# STM32H730_PINOUT.net
KiCad netlist of a schematic drawn in Altium Designer
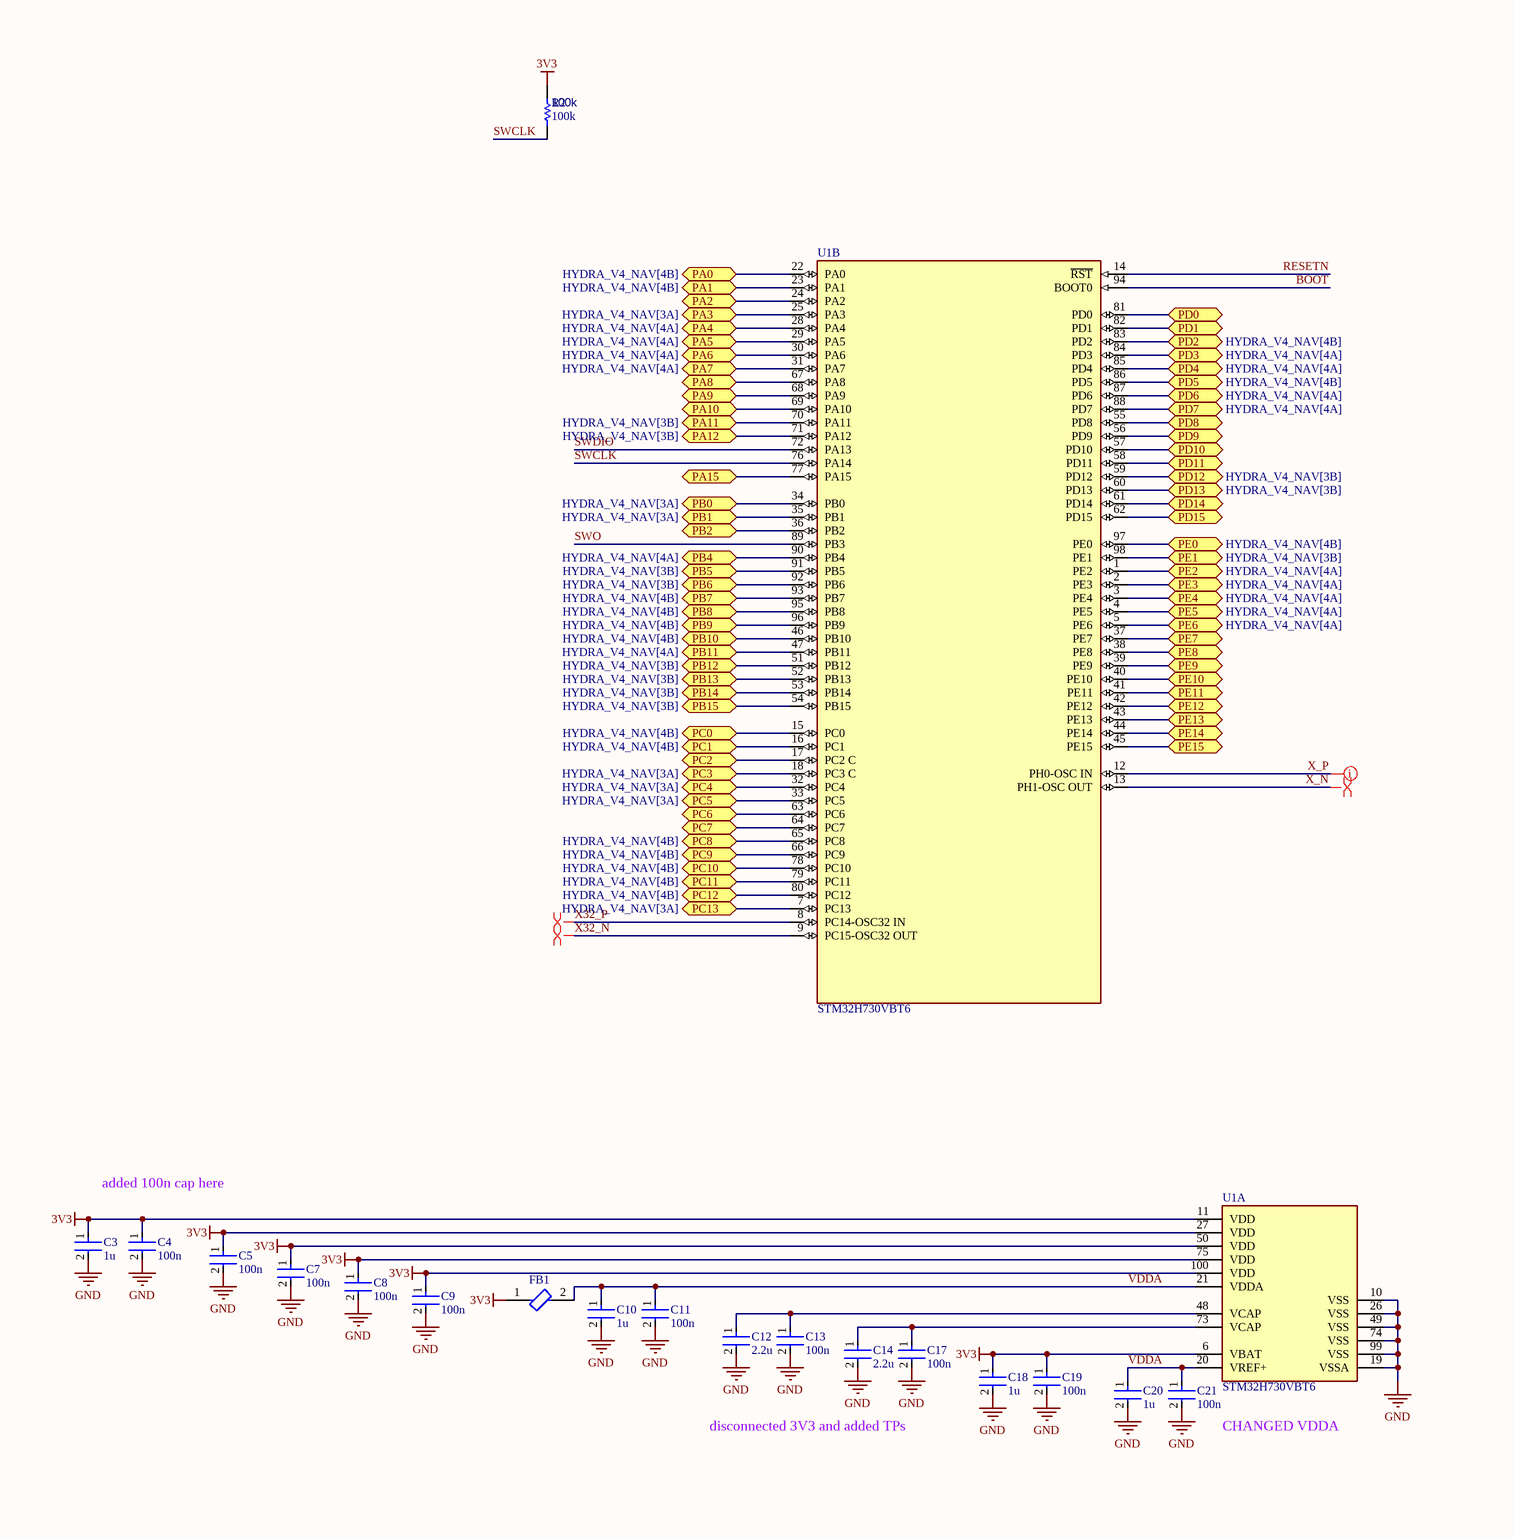
[diagram p0: STM32H730_PINOUT.SchDoc, left]
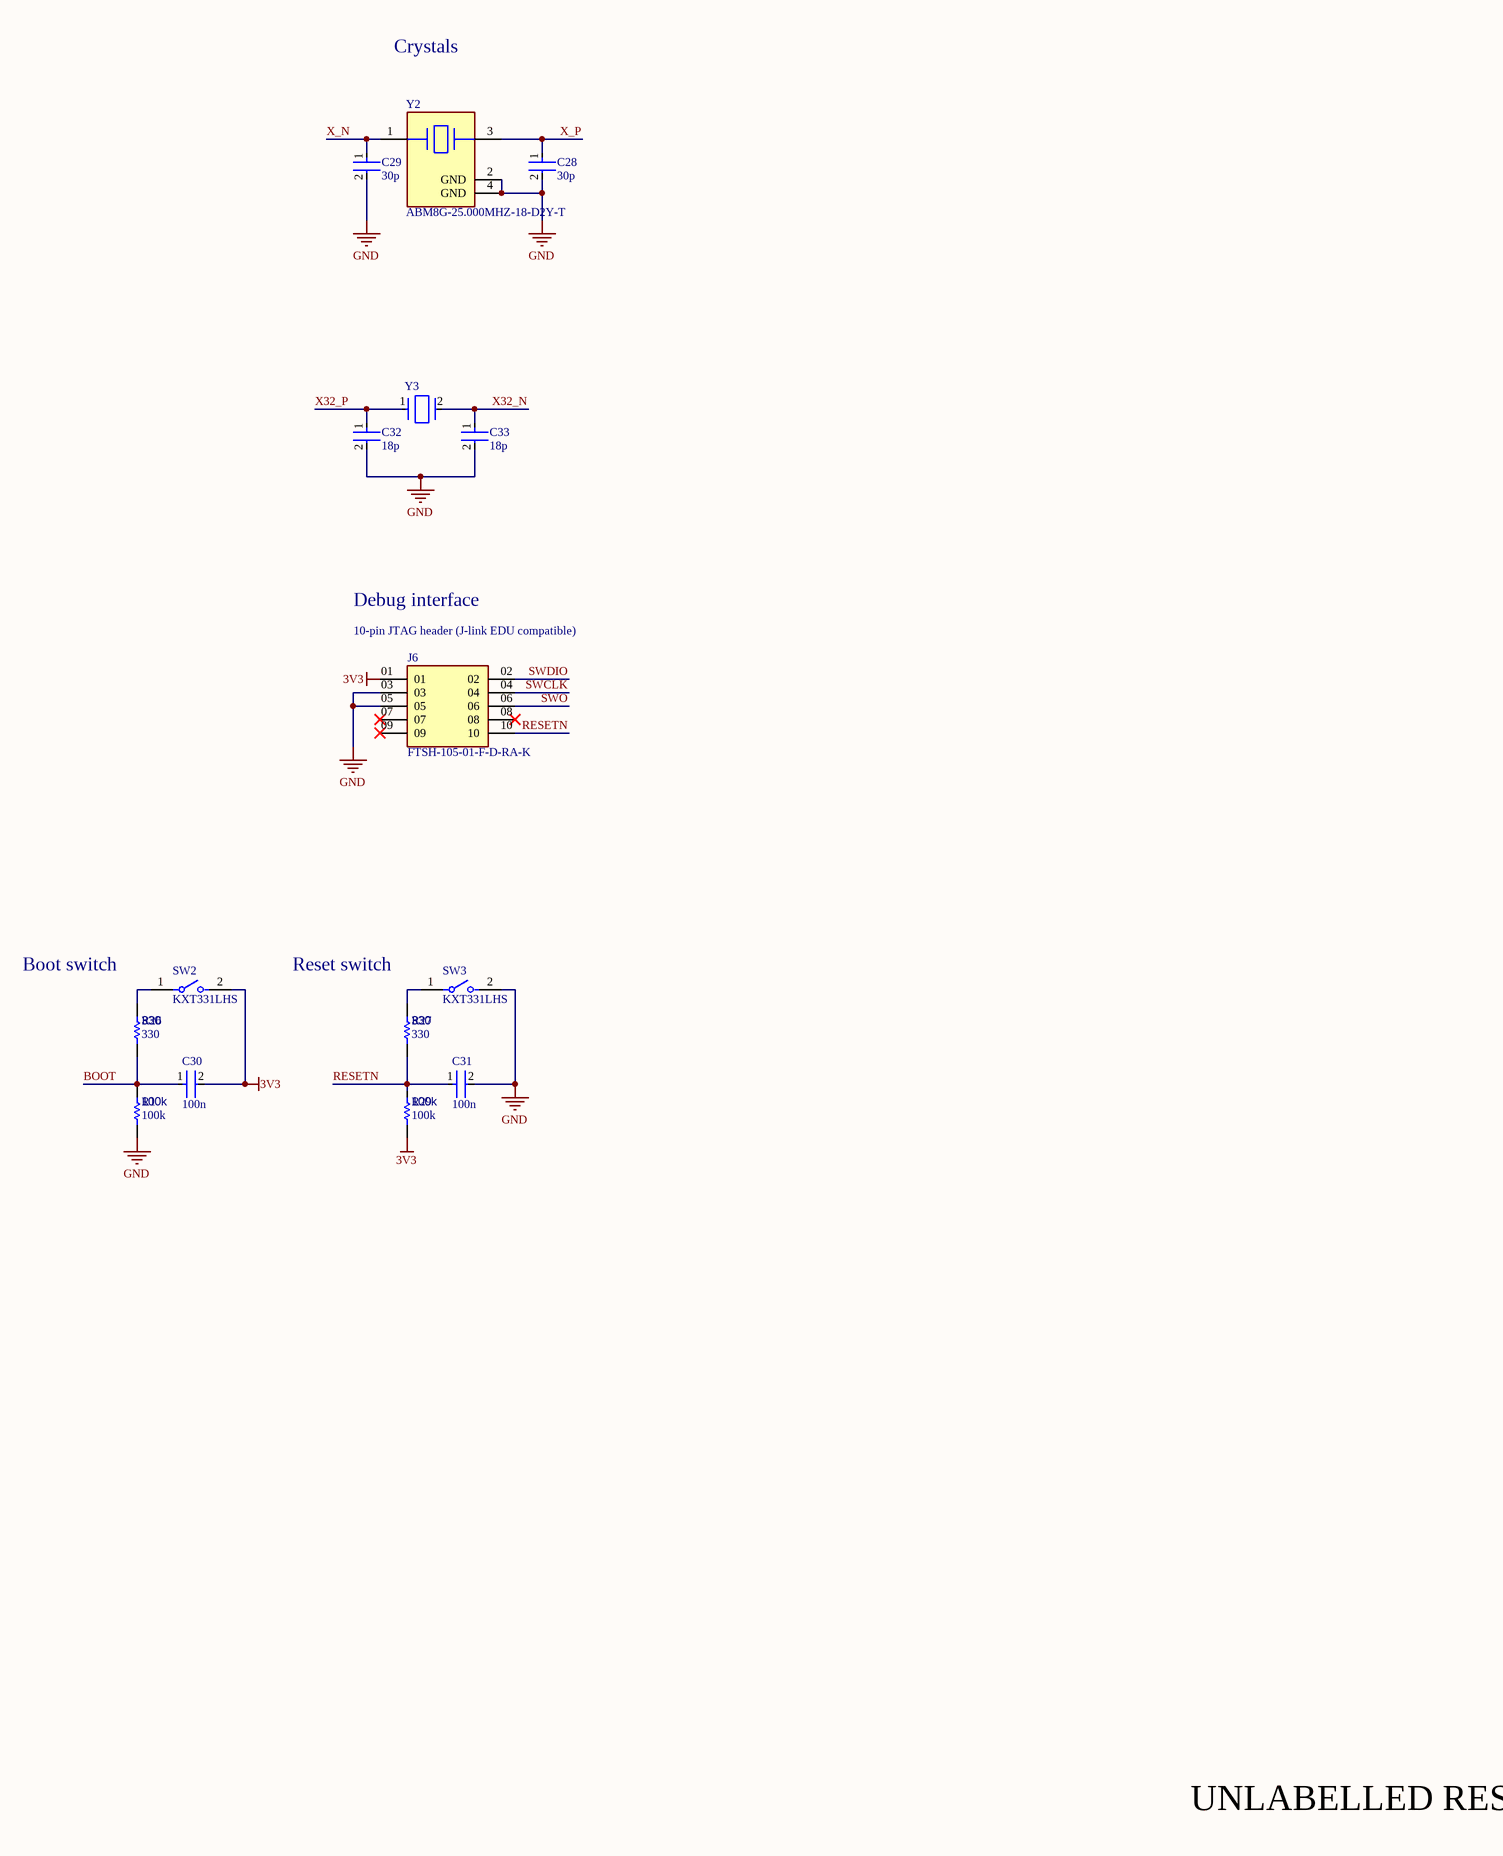
[diagram p1: STM32H730_PINOUT.SchDoc, right]

(export (version "E")
  (design (tool "Eeschema 10.0.6"))
  (components
    (comp (ref "C3")
      (value "1u")
      (footprint "FP-0402-L_1_0_0_05-W_0_5-IPC_A")
      (description "LARGE PADS, 0402 CAP, CHANGE COMMENT TO MATCH REAL P/N")
      (libsource (lib "Space Concordia") (part "b4654b650e69147ec39a6b967a45e02"))
    )
    (comp (ref "C4")
      (value "100n")
      (footprint "FP-0402-L_1_0_0_05-W_0_5-IPC_A")
      (description "LARGE PADS, 0402 CAP, CHANGE COMMENT TO MATCH REAL P/N")
      (libsource (lib "Space Concordia") (part "b4654b650e69147ec39a6b967a45e02"))
    )
    (comp (ref "C5")
      (value "100n")
      (footprint "FP-0402-L_1_0_0_05-W_0_5-IPC_A")
      (description "LARGE PADS, 0402 CAP, CHANGE COMMENT TO MATCH REAL P/N")
      (libsource (lib "Space Concordia") (part "b4654b650e69147ec39a6b967a45e02"))
    )
    (comp (ref "C7")
      (value "100n")
      (footprint "FP-0402-L_1_0_0_05-W_0_5-IPC_A")
      (description "LARGE PADS, 0402 CAP, CHANGE COMMENT TO MATCH REAL P/N")
      (libsource (lib "Space Concordia") (part "b4654b650e69147ec39a6b967a45e02"))
    )
    (comp (ref "C8")
      (value "100n")
      (footprint "FP-0402-L_1_0_0_05-W_0_5-IPC_A")
      (description "LARGE PADS, 0402 CAP, CHANGE COMMENT TO MATCH REAL P/N")
      (libsource (lib "Space Concordia") (part "b4654b650e69147ec39a6b967a45e02"))
    )
    (comp (ref "C9")
      (value "100n")
      (footprint "FP-0402-L_1_0_0_05-W_0_5-IPC_A")
      (description "LARGE PADS, 0402 CAP, CHANGE COMMENT TO MATCH REAL P/N")
      (libsource (lib "Space Concordia") (part "b4654b650e69147ec39a6b967a45e02"))
    )
    (comp (ref "C10")
      (value "1u")
      (footprint "FP-0402-L_1_0_0_05-W_0_5-IPC_A")
      (description "LARGE PADS, 0402 CAP, CHANGE COMMENT TO MATCH REAL P/N")
      (libsource (lib "Space Concordia") (part "b4654b650e69147ec39a6b967a45e02"))
    )
    (comp (ref "C11")
      (value "100n")
      (footprint "FP-0402-L_1_0_0_05-W_0_5-IPC_A")
      (description "LARGE PADS, 0402 CAP, CHANGE COMMENT TO MATCH REAL P/N")
      (libsource (lib "Space Concordia") (part "b4654b650e69147ec39a6b967a45e02"))
    )
    (comp (ref "C12")
      (value "2.2u")
      (footprint "FP-0402-L_1_0_0_05-W_0_5-IPC_A")
      (description "LARGE PADS, 0402 CAP, CHANGE COMMENT TO MATCH REAL P/N")
      (libsource (lib "Space Concordia") (part "b4654b650e69147ec39a6b967a45e02"))
    )
    (comp (ref "C13")
      (value "100n")
      (footprint "FP-0402-L_1_0_0_05-W_0_5-IPC_A")
      (description "LARGE PADS, 0402 CAP, CHANGE COMMENT TO MATCH REAL P/N")
      (libsource (lib "Space Concordia") (part "b4654b650e69147ec39a6b967a45e02"))
    )
    (comp (ref "C14")
      (value "2.2u")
      (footprint "FP-0402-L_1_0_0_05-W_0_5-IPC_A")
      (description "LARGE PADS, 0402 CAP, CHANGE COMMENT TO MATCH REAL P/N")
      (libsource (lib "Space Concordia") (part "b4654b650e69147ec39a6b967a45e02"))
    )
    (comp (ref "C17")
      (value "100n")
      (footprint "FP-0402-L_1_0_0_05-W_0_5-IPC_A")
      (description "LARGE PADS, 0402 CAP, CHANGE COMMENT TO MATCH REAL P/N")
      (libsource (lib "Space Concordia") (part "b4654b650e69147ec39a6b967a45e02"))
    )
    (comp (ref "C18")
      (value "1u")
      (footprint "FP-0402-L_1_0_0_05-W_0_5-IPC_A")
      (description "LARGE PADS, 0402 CAP, CHANGE COMMENT TO MATCH REAL P/N")
      (libsource (lib "Space Concordia") (part "b4654b650e69147ec39a6b967a45e02"))
    )
    (comp (ref "C19")
      (value "100n")
      (footprint "FP-0402-L_1_0_0_05-W_0_5-IPC_A")
      (description "LARGE PADS, 0402 CAP, CHANGE COMMENT TO MATCH REAL P/N")
      (libsource (lib "Space Concordia") (part "b4654b650e69147ec39a6b967a45e02"))
    )
    (comp (ref "C20")
      (value "1u")
      (footprint "FP-0402-L_1_0_0_05-W_0_5-IPC_A")
      (description "LARGE PADS, 0402 CAP, CHANGE COMMENT TO MATCH REAL P/N")
      (libsource (lib "Space Concordia") (part "b4654b650e69147ec39a6b967a45e02"))
    )
    (comp (ref "C21")
      (value "100n")
      (footprint "FP-0402-L_1_0_0_05-W_0_5-IPC_A")
      (description "LARGE PADS, 0402 CAP, CHANGE COMMENT TO MATCH REAL P/N")
      (libsource (lib "Space Concordia") (part "b4654b650e69147ec39a6b967a45e02"))
    )
    (comp (ref "C28")
      (value "30p")
      (footprint "FP-0402-L_1_0_0_05-W_0_5-IPC_A")
      (description "LARGE PADS, 0402 CAP, CHANGE COMMENT TO MATCH REAL P/N")
      (libsource (lib "Space Concordia") (part "b4654b650e69147ec39a6b967a45e02"))
    )
    (comp (ref "C29")
      (value "30p")
      (footprint "FP-0402-L_1_0_0_05-W_0_5-IPC_A")
      (description "LARGE PADS, 0402 CAP, CHANGE COMMENT TO MATCH REAL P/N")
      (libsource (lib "Space Concordia") (part "b4654b650e69147ec39a6b967a45e02"))
    )
    (comp (ref "C30")
      (value "100n")
      (footprint "FP-0402-L_1_0_0_05-W_0_5-IPC_A")
      (description "LARGE PADS, 0402 CAP, CHANGE COMMENT TO MATCH REAL P/N")
      (libsource (lib "Space Concordia") (part "b4654b650e69147ec39a6b967a45e02"))
    )
    (comp (ref "C31")
      (value "100n")
      (footprint "FP-0402-L_1_0_0_05-W_0_5-IPC_A")
      (description "LARGE PADS, 0402 CAP, CHANGE COMMENT TO MATCH REAL P/N")
      (libsource (lib "Space Concordia") (part "b4654b650e69147ec39a6b967a45e02"))
    )
    (comp (ref "C32")
      (value "18p")
      (footprint "FP-0402-L_1_0_0_05-W_0_5-IPC_A")
      (description "LARGE PADS, 0402 CAP, CHANGE COMMENT TO MATCH REAL P/N")
      (libsource (lib "Space Concordia") (part "b4654b650e69147ec39a6b967a45e02"))
    )
    (comp (ref "C33")
      (value "18p")
      (footprint "FP-0402-L_1_0_0_05-W_0_5-IPC_A")
      (description "LARGE PADS, 0402 CAP, CHANGE COMMENT TO MATCH REAL P/N")
      (libsource (lib "Space Concordia") (part "b4654b650e69147ec39a6b967a45e02"))
    )
    (comp (ref "FB1")
      (value "BLM15PX601SN1D")
      (footprint "FP-BLM15-0_05-MFG")
      (description "Chip Ferrite Bead, 0402, 600Ω @ 100MHz, 0.23Ω, 25%, 900mA")
      (fields (field (name "TOLERANCE") "25%"))
      (libsource (lib "Altium Content Vault") (part "5f30dd21d616792df468990f7003faa"))
    )
    (comp (ref "J6")
      (value "FTSH-105-01-F-D-RA-K")
      (footprint "FTSH-105-01-F-D-RA-K-Footprint-1")
      (libsource (lib "Space Concordia") (part "FTSH-105-01-F-D-RA-K-Symbol-1"))
    )
    (comp (ref "R1")
      (value "100k")
      (footprint "R0603B")
      (description "Resistor")
      (fields (field (name "ALTIUM_VALUE") "100k"))
      (libsource (lib "Space Concordia") (part "Resistor"))
    )
    (comp (ref "R2")
      (value "100k")
      (footprint "R0603B")
      (description "Resistor")
      (fields (field (name "ALTIUM_VALUE") "100k"))
      (libsource (lib "Space Concordia") (part "Resistor"))
    )
    (comp (ref "R26")
      (value "330")
      (footprint "R0603B")
      (description "Resistor")
      (fields (field (name "ALTIUM_VALUE") "330"))
      (libsource (lib "Space Concordia") (part "Resistor"))
    )
    (comp (ref "R27")
      (value "330")
      (footprint "R0603B")
      (description "Resistor")
      (fields (field (name "ALTIUM_VALUE") "330"))
      (libsource (lib "Space Concordia") (part "Resistor"))
    )
    (comp (ref "R29")
      (value "100k")
      (footprint "R0603B")
      (description "Resistor")
      (fields (field (name "ALTIUM_VALUE") "100k"))
      (libsource (lib "Space Concordia") (part "Resistor"))
    )
    (comp (ref "SW2")
      (value "KXT331LHS")
      (footprint "FP-KXT331LHS-MFG")
      (description "SWITCH TACTILE SPST-NO 0.02A 15V")
      (libsource (lib "Altium Content Vault") (part "bb27bde45df87f1f469753f287ef5ae"))
    )
    (comp (ref "SW3")
      (value "KXT331LHS")
      (footprint "FP-KXT331LHS-MFG")
      (description "SWITCH TACTILE SPST-NO 0.02A 15V")
      (libsource (lib "Altium Content Vault") (part "bb27bde45df87f1f469753f287ef5ae"))
    )
    (comp (ref "U1")
      (value "STM32H730VBT6")
      (footprint "FP-LQFP100-1L-IPC_C")
      (description "IC MCU 32BIT 128KB FLASH 100LQFP")
      (libsource (lib "Altium Content Vault") (part "44dc6501260a4d92b846760feb66c20"))
    )
    (comp (ref "Y2")
      (value "ABM8G-25.000MHZ-18-D2Y-T")
      (footprint "FP-ABM8G-MFG")
      (description "Crystal 25MHz ±20ppm (Tol) ±30ppm (Stability) 18pF FUND 60Ω 4-Pin SMD T/R")
      (fields (field (name "TOLERANCE") "20ppm"))
      (libsource (lib "Altium Content Vault") (part "48e526d86b7f2615d98721063c72f49"))
    )
    (comp (ref "Y3")
      (value "ECS-.327-12.5-1210-TR")
      (footprint "FP-ECX-1210-MFG")
      (description "CRYSTAL 32.7680KHZ 12.5PF SMD")
      (fields
        (field (name "OCTOPART") "https://octopart.com/ecs-.327-12.5-1210-tr-ecs+international-81221340")
        (field (name "TOLERANCE") "20ppm")
      )
      (libsource (lib "Altium Content Vault") (part "99724985039315a44fd0d1401b84e49"))
    )
  )
  (nets
    (net (code "1") (name "/BOOT") (class "Default")
      (node (ref "C30") (pin "1") (pinfunction "1_1") (pintype "passive"))
      (node (ref "R1") (pin "1") (pinfunction "1_1") (pintype "passive"))
      (node (ref "R26") (pin "2") (pinfunction "2_2") (pintype "passive"))
      (node (ref "U1") (pin "94") (pinfunction "BOOT0_94") (pintype "input"))
    )
    (net (code "2") (name "/PA0") (class "Default")
      (node (ref "U1") (pin "22") (pinfunction "PA0_22") (pintype "bidirectional"))
    )
    (net (code "3") (name "/PA1") (class "Default")
      (node (ref "U1") (pin "23") (pinfunction "PA1_23") (pintype "bidirectional"))
    )
    (net (code "4") (name "/PA2") (class "Default")
      (node (ref "U1") (pin "24") (pinfunction "PA2_24") (pintype "bidirectional"))
    )
    (net (code "5") (name "/PA3") (class "Default")
      (node (ref "U1") (pin "25") (pinfunction "PA3_25") (pintype "bidirectional"))
    )
    (net (code "6") (name "/PA4") (class "Default")
      (node (ref "U1") (pin "28") (pinfunction "PA4_28") (pintype "bidirectional"))
    )
    (net (code "7") (name "/PA5") (class "Default")
      (node (ref "U1") (pin "29") (pinfunction "PA5_29") (pintype "bidirectional"))
    )
    (net (code "8") (name "/PA6") (class "Default")
      (node (ref "U1") (pin "30") (pinfunction "PA6_30") (pintype "bidirectional"))
    )
    (net (code "9") (name "/PA7") (class "Default")
      (node (ref "U1") (pin "31") (pinfunction "PA7_31") (pintype "bidirectional"))
    )
    (net (code "10") (name "/PA8") (class "Default")
      (node (ref "U1") (pin "67") (pinfunction "PA8_67") (pintype "bidirectional"))
    )
    (net (code "11") (name "/PA9") (class "Default")
      (node (ref "U1") (pin "68") (pinfunction "PA9_68") (pintype "bidirectional"))
    )
    (net (code "12") (name "/PA10") (class "Default")
      (node (ref "U1") (pin "69") (pinfunction "PA10_69") (pintype "bidirectional"))
    )
    (net (code "13") (name "/PA11") (class "Default")
      (node (ref "U1") (pin "70") (pinfunction "PA11_70") (pintype "bidirectional"))
    )
    (net (code "14") (name "/PA12") (class "Default")
      (node (ref "U1") (pin "71") (pinfunction "PA12_71") (pintype "bidirectional"))
    )
    (net (code "15") (name "/PA15") (class "Default")
      (node (ref "U1") (pin "77") (pinfunction "PA15_77") (pintype "bidirectional"))
    )
    (net (code "16") (name "/PB0") (class "Default")
      (node (ref "U1") (pin "34") (pinfunction "PB0_34") (pintype "bidirectional"))
    )
    (net (code "17") (name "/PB1") (class "Default")
      (node (ref "U1") (pin "35") (pinfunction "PB1_35") (pintype "bidirectional"))
    )
    (net (code "18") (name "/PB2") (class "Default")
      (node (ref "U1") (pin "36") (pinfunction "PB2_36") (pintype "bidirectional"))
    )
    (net (code "19") (name "/PB4") (class "Default")
      (node (ref "U1") (pin "90") (pinfunction "PB4_90") (pintype "bidirectional"))
    )
    (net (code "20") (name "/PB5") (class "Default")
      (node (ref "U1") (pin "91") (pinfunction "PB5_91") (pintype "bidirectional"))
    )
    (net (code "21") (name "/PB6") (class "Default")
      (node (ref "U1") (pin "92") (pinfunction "PB6_92") (pintype "bidirectional"))
    )
    (net (code "22") (name "/PB7") (class "Default")
      (node (ref "U1") (pin "93") (pinfunction "PB7_93") (pintype "bidirectional"))
    )
    (net (code "23") (name "/PB8") (class "Default")
      (node (ref "U1") (pin "95") (pinfunction "PB8_95") (pintype "bidirectional"))
    )
    (net (code "24") (name "/PB9") (class "Default")
      (node (ref "U1") (pin "96") (pinfunction "PB9_96") (pintype "bidirectional"))
    )
    (net (code "25") (name "/PB10") (class "Default")
      (node (ref "U1") (pin "46") (pinfunction "PB10_46") (pintype "bidirectional"))
    )
    (net (code "26") (name "/PB11") (class "Default")
      (node (ref "U1") (pin "47") (pinfunction "PB11_47") (pintype "bidirectional"))
    )
    (net (code "27") (name "/PB12") (class "Default")
      (node (ref "U1") (pin "51") (pinfunction "PB12_51") (pintype "bidirectional"))
    )
    (net (code "28") (name "/PB13") (class "Default")
      (node (ref "U1") (pin "52") (pinfunction "PB13_52") (pintype "bidirectional"))
    )
    (net (code "29") (name "/PB14") (class "Default")
      (node (ref "U1") (pin "53") (pinfunction "PB14_53") (pintype "bidirectional"))
    )
    (net (code "30") (name "/PB15") (class "Default")
      (node (ref "U1") (pin "54") (pinfunction "PB15_54") (pintype "bidirectional"))
    )
    (net (code "31") (name "/PC0") (class "Default")
      (node (ref "U1") (pin "15") (pinfunction "PC0_15") (pintype "bidirectional"))
    )
    (net (code "32") (name "/PC1") (class "Default")
      (node (ref "U1") (pin "16") (pinfunction "PC1_16") (pintype "bidirectional"))
    )
    (net (code "33") (name "/PC2") (class "Default")
      (node (ref "U1") (pin "17") (pinfunction "PC2_C_17") (pintype "bidirectional"))
    )
    (net (code "34") (name "/PC3") (class "Default")
      (node (ref "U1") (pin "18") (pinfunction "PC3_C_18") (pintype "bidirectional"))
    )
    (net (code "35") (name "/PC4") (class "Default")
      (node (ref "U1") (pin "32") (pinfunction "PC4_32") (pintype "bidirectional"))
    )
    (net (code "36") (name "/PC5") (class "Default")
      (node (ref "U1") (pin "33") (pinfunction "PC5_33") (pintype "bidirectional"))
    )
    (net (code "37") (name "/PC6") (class "Default")
      (node (ref "U1") (pin "63") (pinfunction "PC6_63") (pintype "bidirectional"))
    )
    (net (code "38") (name "/PC7") (class "Default")
      (node (ref "U1") (pin "64") (pinfunction "PC7_64") (pintype "bidirectional"))
    )
    (net (code "39") (name "/PC8") (class "Default")
      (node (ref "U1") (pin "65") (pinfunction "PC8_65") (pintype "bidirectional"))
    )
    (net (code "40") (name "/PC9") (class "Default")
      (node (ref "U1") (pin "66") (pinfunction "PC9_66") (pintype "bidirectional"))
    )
    (net (code "41") (name "/PC10") (class "Default")
      (node (ref "U1") (pin "78") (pinfunction "PC10_78") (pintype "bidirectional"))
    )
    (net (code "42") (name "/PC11") (class "Default")
      (node (ref "U1") (pin "79") (pinfunction "PC11_79") (pintype "bidirectional"))
    )
    (net (code "43") (name "/PC12") (class "Default")
      (node (ref "U1") (pin "80") (pinfunction "PC12_80") (pintype "bidirectional"))
    )
    (net (code "44") (name "/PC13") (class "Default")
      (node (ref "U1") (pin "7") (pinfunction "PC13_7") (pintype "bidirectional"))
    )
    (net (code "45") (name "/PD0") (class "Default")
      (node (ref "U1") (pin "81") (pinfunction "PD0_81") (pintype "bidirectional"))
    )
    (net (code "46") (name "/PD1") (class "Default")
      (node (ref "U1") (pin "82") (pinfunction "PD1_82") (pintype "bidirectional"))
    )
    (net (code "47") (name "/PD2") (class "Default")
      (node (ref "U1") (pin "83") (pinfunction "PD2_83") (pintype "bidirectional"))
    )
    (net (code "48") (name "/PD3") (class "Default")
      (node (ref "U1") (pin "84") (pinfunction "PD3_84") (pintype "bidirectional"))
    )
    (net (code "49") (name "/PD4") (class "Default")
      (node (ref "U1") (pin "85") (pinfunction "PD4_85") (pintype "bidirectional"))
    )
    (net (code "50") (name "/PD5") (class "Default")
      (node (ref "U1") (pin "86") (pinfunction "PD5_86") (pintype "bidirectional"))
    )
    (net (code "51") (name "/PD6") (class "Default")
      (node (ref "U1") (pin "87") (pinfunction "PD6_87") (pintype "bidirectional"))
    )
    (net (code "52") (name "/PD7") (class "Default")
      (node (ref "U1") (pin "88") (pinfunction "PD7_88") (pintype "bidirectional"))
    )
    (net (code "53") (name "/PD8") (class "Default")
      (node (ref "U1") (pin "55") (pinfunction "PD8_55") (pintype "bidirectional"))
    )
    (net (code "54") (name "/PD9") (class "Default")
      (node (ref "U1") (pin "56") (pinfunction "PD9_56") (pintype "bidirectional"))
    )
    (net (code "55") (name "/PD10") (class "Default")
      (node (ref "U1") (pin "57") (pinfunction "PD10_57") (pintype "bidirectional"))
    )
    (net (code "56") (name "/PD11") (class "Default")
      (node (ref "U1") (pin "58") (pinfunction "PD11_58") (pintype "bidirectional"))
    )
    (net (code "57") (name "/PD12") (class "Default")
      (node (ref "U1") (pin "59") (pinfunction "PD12_59") (pintype "bidirectional"))
    )
    (net (code "58") (name "/PD13") (class "Default")
      (node (ref "U1") (pin "60") (pinfunction "PD13_60") (pintype "bidirectional"))
    )
    (net (code "59") (name "/PD14") (class "Default")
      (node (ref "U1") (pin "61") (pinfunction "PD14_61") (pintype "bidirectional"))
    )
    (net (code "60") (name "/PD15") (class "Default")
      (node (ref "U1") (pin "62") (pinfunction "PD15_62") (pintype "bidirectional"))
    )
    (net (code "61") (name "/PE0") (class "Default")
      (node (ref "U1") (pin "97") (pinfunction "PE0_97") (pintype "bidirectional"))
    )
    (net (code "62") (name "/PE1") (class "Default")
      (node (ref "U1") (pin "98") (pinfunction "PE1_98") (pintype "bidirectional"))
    )
    (net (code "63") (name "/PE2") (class "Default")
      (node (ref "U1") (pin "1") (pinfunction "PE2_1") (pintype "bidirectional"))
    )
    (net (code "64") (name "/PE3") (class "Default")
      (node (ref "U1") (pin "2") (pinfunction "PE3_2") (pintype "bidirectional"))
    )
    (net (code "65") (name "/PE4") (class "Default")
      (node (ref "U1") (pin "3") (pinfunction "PE4_3") (pintype "bidirectional"))
    )
    (net (code "66") (name "/PE5") (class "Default")
      (node (ref "U1") (pin "4") (pinfunction "PE5_4") (pintype "bidirectional"))
    )
    (net (code "67") (name "/PE6") (class "Default")
      (node (ref "U1") (pin "5") (pinfunction "PE6_5") (pintype "bidirectional"))
    )
    (net (code "68") (name "/PE7") (class "Default")
      (node (ref "U1") (pin "37") (pinfunction "PE7_37") (pintype "bidirectional"))
    )
    (net (code "69") (name "/PE8") (class "Default")
      (node (ref "U1") (pin "38") (pinfunction "PE8_38") (pintype "bidirectional"))
    )
    (net (code "70") (name "/PE9") (class "Default")
      (node (ref "U1") (pin "39") (pinfunction "PE9_39") (pintype "bidirectional"))
    )
    (net (code "71") (name "/PE10") (class "Default")
      (node (ref "U1") (pin "40") (pinfunction "PE10_40") (pintype "bidirectional"))
    )
    (net (code "72") (name "/PE11") (class "Default")
      (node (ref "U1") (pin "41") (pinfunction "PE11_41") (pintype "bidirectional"))
    )
    (net (code "73") (name "/PE12") (class "Default")
      (node (ref "U1") (pin "42") (pinfunction "PE12_42") (pintype "bidirectional"))
    )
    (net (code "74") (name "/PE13") (class "Default")
      (node (ref "U1") (pin "43") (pinfunction "PE13_43") (pintype "bidirectional"))
    )
    (net (code "75") (name "/PE14") (class "Default")
      (node (ref "U1") (pin "44") (pinfunction "PE14_44") (pintype "bidirectional"))
    )
    (net (code "76") (name "/PE15") (class "Default")
      (node (ref "U1") (pin "45") (pinfunction "PE15_45") (pintype "bidirectional"))
    )
    (net (code "77") (name "/RESETN") (class "Default")
      (node (ref "C31") (pin "1") (pinfunction "1_1") (pintype "passive"))
      (node (ref "J6") (pin "10") (pinfunction "10_10") (pintype "passive"))
      (node (ref "R27") (pin "2") (pinfunction "2_2") (pintype "passive"))
      (node (ref "R29") (pin "1") (pinfunction "1_1") (pintype "passive"))
      (node (ref "U1") (pin "14") (pinfunction "~{RST}_14") (pintype "input"))
    )
    (net (code "78") (name "/SWCLK") (class "Default")
      (node (ref "J6") (pin "04") (pinfunction "04_04") (pintype "passive"))
      (node (ref "R2") (pin "2") (pinfunction "2_2") (pintype "passive"))
      (node (ref "U1") (pin "76") (pinfunction "PA14_76") (pintype "bidirectional"))
    )
    (net (code "79") (name "/SWDIO") (class "Default")
      (node (ref "J6") (pin "02") (pinfunction "02_02") (pintype "passive"))
      (node (ref "U1") (pin "72") (pinfunction "PA13_72") (pintype "bidirectional"))
    )
    (net (code "80") (name "/SWO") (class "Default")
      (node (ref "J6") (pin "06") (pinfunction "06_06") (pintype "passive"))
      (node (ref "U1") (pin "89") (pinfunction "PB3_89") (pintype "bidirectional"))
    )
    (net (code "81") (name "/VDDA") (class "Default")
      (node (ref "C10") (pin "1") (pinfunction "1_1") (pintype "passive"))
      (node (ref "C11") (pin "1") (pinfunction "1_1") (pintype "passive"))
      (node (ref "C20") (pin "1") (pinfunction "1_1") (pintype "passive"))
      (node (ref "C21") (pin "1") (pinfunction "1_1") (pintype "passive"))
      (node (ref "FB1") (pin "2") (pinfunction "2_2") (pintype "passive"))
      (node (ref "U1") (pin "20") (pinfunction "VREF+_20") (pintype "power_in"))
      (node (ref "U1") (pin "21") (pinfunction "VDDA_21") (pintype "power_in"))
    )
    (net (code "82") (name "/X32_N") (class "Default")
      (node (ref "C33") (pin "1") (pinfunction "1_1") (pintype "passive"))
      (node (ref "U1") (pin "9") (pinfunction "PC15-OSC32_OUT_9") (pintype "bidirectional"))
      (node (ref "Y3") (pin "2") (pinfunction "Out/In_2") (pintype "passive"))
    )
    (net (code "83") (name "/X32_P") (class "Default")
      (node (ref "C32") (pin "1") (pinfunction "1_1") (pintype "passive"))
      (node (ref "U1") (pin "8") (pinfunction "PC14-OSC32_IN_8") (pintype "bidirectional"))
      (node (ref "Y3") (pin "1") (pinfunction "In/Out_1") (pintype "passive"))
    )
    (net (code "84") (name "/X_N") (class "Default")
      (node (ref "C29") (pin "1") (pinfunction "1_1") (pintype "passive"))
      (node (ref "U1") (pin "13") (pinfunction "PH1-OSC_OUT_13") (pintype "bidirectional"))
      (node (ref "Y2") (pin "1") (pinfunction "1_1") (pintype "passive"))
    )
    (net (code "85") (name "/X_P") (class "Default")
      (node (ref "C28") (pin "1") (pinfunction "1_1") (pintype "passive"))
      (node (ref "U1") (pin "12") (pinfunction "PH0-OSC_IN_12") (pintype "bidirectional"))
      (node (ref "Y2") (pin "3") (pinfunction "3_3") (pintype "passive"))
    )
    (net (code "86") (name "3V3") (class "Default")
      (node (ref "C18") (pin "1") (pinfunction "1_1") (pintype "passive"))
      (node (ref "C19") (pin "1") (pinfunction "1_1") (pintype "passive"))
      (node (ref "C3") (pin "1") (pinfunction "1_1") (pintype "passive"))
      (node (ref "C30") (pin "2") (pinfunction "2_2") (pintype "passive"))
      (node (ref "C4") (pin "1") (pinfunction "1_1") (pintype "passive"))
      (node (ref "C5") (pin "1") (pinfunction "1_1") (pintype "passive"))
      (node (ref "C7") (pin "1") (pinfunction "1_1") (pintype "passive"))
      (node (ref "C8") (pin "1") (pinfunction "1_1") (pintype "passive"))
      (node (ref "C9") (pin "1") (pinfunction "1_1") (pintype "passive"))
      (node (ref "FB1") (pin "1") (pinfunction "1_1") (pintype "passive"))
      (node (ref "J6") (pin "01") (pinfunction "01_01") (pintype "passive"))
      (node (ref "R2") (pin "1") (pinfunction "1_1") (pintype "passive"))
      (node (ref "R29") (pin "2") (pinfunction "2_2") (pintype "passive"))
      (node (ref "SW2") (pin "2") (pinfunction "2_2") (pintype "passive"))
      (node (ref "U1") (pin "100") (pinfunction "VDD_100") (pintype "power_in"))
      (node (ref "U1") (pin "11") (pinfunction "VDD_11") (pintype "power_in"))
      (node (ref "U1") (pin "27") (pinfunction "VDD_27") (pintype "power_in"))
      (node (ref "U1") (pin "50") (pinfunction "VDD_50") (pintype "power_in"))
      (node (ref "U1") (pin "6") (pinfunction "VBAT_6") (pintype "power_in"))
      (node (ref "U1") (pin "75") (pinfunction "VDD_75") (pintype "power_in"))
    )
    (net (code "87") (name "GND") (class "Default")
      (node (ref "C10") (pin "2") (pinfunction "2_2") (pintype "passive"))
      (node (ref "C11") (pin "2") (pinfunction "2_2") (pintype "passive"))
      (node (ref "C12") (pin "2") (pinfunction "2_2") (pintype "passive"))
      (node (ref "C13") (pin "2") (pinfunction "2_2") (pintype "passive"))
      (node (ref "C14") (pin "2") (pinfunction "2_2") (pintype "passive"))
      (node (ref "C17") (pin "2") (pinfunction "2_2") (pintype "passive"))
      (node (ref "C18") (pin "2") (pinfunction "2_2") (pintype "passive"))
      (node (ref "C19") (pin "2") (pinfunction "2_2") (pintype "passive"))
      (node (ref "C20") (pin "2") (pinfunction "2_2") (pintype "passive"))
      (node (ref "C21") (pin "2") (pinfunction "2_2") (pintype "passive"))
      (node (ref "C28") (pin "2") (pinfunction "2_2") (pintype "passive"))
      (node (ref "C29") (pin "2") (pinfunction "2_2") (pintype "passive"))
      (node (ref "C3") (pin "2") (pinfunction "2_2") (pintype "passive"))
      (node (ref "C31") (pin "2") (pinfunction "2_2") (pintype "passive"))
      (node (ref "C32") (pin "2") (pinfunction "2_2") (pintype "passive"))
      (node (ref "C33") (pin "2") (pinfunction "2_2") (pintype "passive"))
      (node (ref "C4") (pin "2") (pinfunction "2_2") (pintype "passive"))
      (node (ref "C5") (pin "2") (pinfunction "2_2") (pintype "passive"))
      (node (ref "C7") (pin "2") (pinfunction "2_2") (pintype "passive"))
      (node (ref "C8") (pin "2") (pinfunction "2_2") (pintype "passive"))
      (node (ref "C9") (pin "2") (pinfunction "2_2") (pintype "passive"))
      (node (ref "J6") (pin "03") (pinfunction "03_03") (pintype "passive"))
      (node (ref "J6") (pin "05") (pinfunction "05_05") (pintype "passive"))
      (node (ref "R1") (pin "2") (pinfunction "2_2") (pintype "passive"))
      (node (ref "SW3") (pin "2") (pinfunction "2_2") (pintype "passive"))
      (node (ref "U1") (pin "10") (pinfunction "VSS_10") (pintype "power_in"))
      (node (ref "U1") (pin "19") (pinfunction "VSSA_19") (pintype "power_in"))
      (node (ref "U1") (pin "26") (pinfunction "VSS_26") (pintype "power_in"))
      (node (ref "U1") (pin "49") (pinfunction "VSS_49") (pintype "power_in"))
      (node (ref "U1") (pin "74") (pinfunction "VSS_74") (pintype "power_in"))
      (node (ref "U1") (pin "99") (pinfunction "VSS_99") (pintype "power_in"))
      (node (ref "Y2") (pin "2") (pinfunction "GND_2") (pintype "power_in"))
      (node (ref "Y2") (pin "4") (pinfunction "GND_4") (pintype "power_in"))
    )
    (net (code "88") (name "Net-(C12-Pad1)") (class "Default")
      (node (ref "C12") (pin "1") (pinfunction "1_1") (pintype "passive"))
      (node (ref "C13") (pin "1") (pinfunction "1_1") (pintype "passive"))
      (node (ref "U1") (pin "48") (pinfunction "VCAP_48") (pintype "power_in"))
    )
    (net (code "89") (name "Net-(C14-Pad1)") (class "Default")
      (node (ref "C14") (pin "1") (pinfunction "1_1") (pintype "passive"))
      (node (ref "C17") (pin "1") (pinfunction "1_1") (pintype "passive"))
      (node (ref "U1") (pin "73") (pinfunction "VCAP_73") (pintype "power_in"))
    )
    (net (code "90") (name "Net-(R26-Pad1)") (class "Default")
      (node (ref "R26") (pin "1") (pinfunction "1_1") (pintype "passive"))
      (node (ref "SW2") (pin "1") (pinfunction "1_1") (pintype "passive"))
    )
    (net (code "91") (name "Net-(R27-Pad1)") (class "Default")
      (node (ref "R27") (pin "1") (pinfunction "1_1") (pintype "passive"))
      (node (ref "SW3") (pin "1") (pinfunction "1_1") (pintype "passive"))
    )
    (net (code "92") (name "unconnected-(J6-Pad07)") (class "Default")
      (node (ref "J6") (pin "07") (pinfunction "07_07") (pintype "passive+no_connect"))
    )
    (net (code "93") (name "unconnected-(J6-Pad08)") (class "Default")
      (node (ref "J6") (pin "08") (pinfunction "08_08") (pintype "passive+no_connect"))
    )
    (net (code "94") (name "unconnected-(J6-Pad09)") (class "Default")
      (node (ref "J6") (pin "09") (pinfunction "09_09") (pintype "passive+no_connect"))
    )
  )
)
